# extension-board.net
KiCad netlist of a schematic drawn in EAGLE
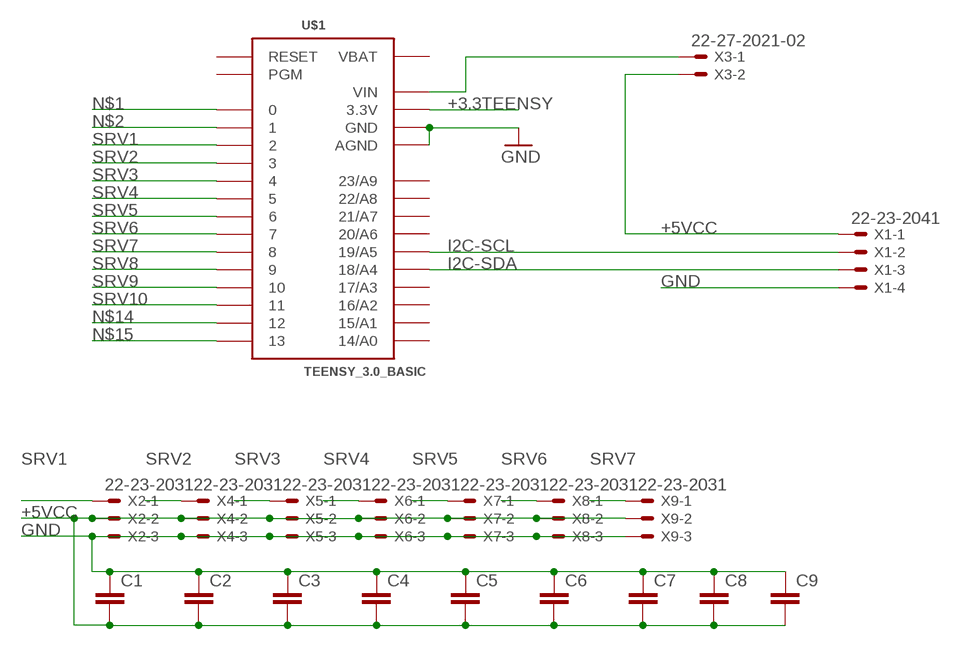
[diagram p0: schematic, sheet 1]

(export (version "E")
  (design (tool "Eeschema 10.0.6"))
  (components
    (comp (ref "C1")
      (value "C-EUC0805K")
      (footprint "eagle-import:C0805K")
      (libsource (lib "eagle-import") (part "C-EUC0805K"))
    )
    (comp (ref "C2")
      (value "C-EUC0805K")
      (footprint "eagle-import:C0805K")
      (libsource (lib "eagle-import") (part "C-EUC0805K"))
    )
    (comp (ref "C3")
      (value "C-EUC0805K")
      (footprint "eagle-import:C0805K")
      (libsource (lib "eagle-import") (part "C-EUC0805K"))
    )
    (comp (ref "C4")
      (value "C-EUC0805K")
      (footprint "eagle-import:C0805K")
      (libsource (lib "eagle-import") (part "C-EUC0805K"))
    )
    (comp (ref "C5")
      (value "C-EUC0805K")
      (footprint "eagle-import:C0805K")
      (libsource (lib "eagle-import") (part "C-EUC0805K"))
    )
    (comp (ref "C6")
      (value "C-EUC0805K")
      (footprint "eagle-import:C0805K")
      (libsource (lib "eagle-import") (part "C-EUC0805K"))
    )
    (comp (ref "C7")
      (value "C-EUC0805K")
      (footprint "eagle-import:C0805K")
      (libsource (lib "eagle-import") (part "C-EUC0805K"))
    )
    (comp (ref "C8")
      (value "C-EUC0805K")
      (footprint "eagle-import:C0805K")
      (libsource (lib "eagle-import") (part "C-EUC0805K"))
    )
    (comp (ref "C9")
      (value "C-EUC0805K")
      (footprint "eagle-import:C0805K")
      (libsource (lib "eagle-import") (part "C-EUC0805K"))
    )
    (comp (ref "U$1")
      (value "TEENSY_3.0_BASIC")
      (footprint "eagle-import:TEENSY_3.0_BASIC")
      (libsource (lib "eagle-import") (part "TEENSY_3.0_BASIC"))
    )
    (comp (ref "X1")
      (value "22-23-2041")
      (footprint "eagle-import:22-23-2041")
      (fields (field (name "MF") "MOLEX"))
      (libsource (lib "eagle-import") (part "22-23-2041"))
    )
    (comp (ref "X2")
      (value "22-23-2031")
      (footprint "eagle-import:22-23-2031")
      (fields (field (name "MF") "MOLEX"))
      (libsource (lib "eagle-import") (part "22-23-2031"))
    )
    (comp (ref "X3")
      (value "22-27-2021-02")
      (footprint "eagle-import:6410-02")
      (libsource (lib "eagle-import") (part "22-?-0227-2021"))
    )
    (comp (ref "X4")
      (value "22-23-2031")
      (footprint "eagle-import:22-23-2031")
      (fields (field (name "MF") "MOLEX"))
      (libsource (lib "eagle-import") (part "22-23-2031"))
    )
    (comp (ref "X5")
      (value "22-23-2031")
      (footprint "eagle-import:22-23-2031")
      (fields (field (name "MF") "MOLEX"))
      (libsource (lib "eagle-import") (part "22-23-2031"))
    )
    (comp (ref "X6")
      (value "22-23-2031")
      (footprint "eagle-import:22-23-2031")
      (fields (field (name "MF") "MOLEX"))
      (libsource (lib "eagle-import") (part "22-23-2031"))
    )
    (comp (ref "X7")
      (value "22-23-2031")
      (footprint "eagle-import:22-23-2031")
      (fields (field (name "MF") "MOLEX"))
      (libsource (lib "eagle-import") (part "22-23-2031"))
    )
    (comp (ref "X8")
      (value "22-23-2031")
      (footprint "eagle-import:22-23-2031")
      (fields (field (name "MF") "MOLEX"))
      (libsource (lib "eagle-import") (part "22-23-2031"))
    )
    (comp (ref "X9")
      (value "22-23-2031")
      (footprint "eagle-import:22-23-2031")
      (fields (field (name "MF") "MOLEX"))
      (libsource (lib "eagle-import") (part "22-23-2031"))
    )
  )
  (nets
    (net (code "1") (name "/+3.3TEENSY") (class "Default")
      (node (ref "U$1") (pin "3.3V") (pinfunction "3.3V_3.3V") (pintype "power_in"))
      (node (ref "U$1") (pin "3.3V1") (pinfunction "3.3V_3.3V1") (pintype "power_in"))
    )
    (net (code "2") (name "/+5VCC") (class "Default")
      (node (ref "C1") (pin "2") (pinfunction "2_2") (pintype "passive"))
      (node (ref "C2") (pin "2") (pinfunction "2_2") (pintype "passive"))
      (node (ref "C3") (pin "2") (pinfunction "2_2") (pintype "passive"))
      (node (ref "C4") (pin "2") (pinfunction "2_2") (pintype "passive"))
      (node (ref "C5") (pin "2") (pinfunction "2_2") (pintype "passive"))
      (node (ref "C6") (pin "2") (pinfunction "2_2") (pintype "passive"))
      (node (ref "C7") (pin "2") (pinfunction "2_2") (pintype "passive"))
      (node (ref "C8") (pin "2") (pinfunction "2_2") (pintype "passive"))
      (node (ref "C9") (pin "2") (pinfunction "2_2") (pintype "passive"))
      (node (ref "X1") (pin "1") (pinfunction "S_1") (pintype "passive"))
      (node (ref "X2") (pin "2") (pinfunction "S_2") (pintype "passive"))
      (node (ref "X3") (pin "2") (pinfunction "S_2") (pintype "passive"))
      (node (ref "X4") (pin "2") (pinfunction "S_2") (pintype "passive"))
      (node (ref "X5") (pin "2") (pinfunction "S_2") (pintype "passive"))
      (node (ref "X6") (pin "2") (pinfunction "S_2") (pintype "passive"))
      (node (ref "X7") (pin "2") (pinfunction "S_2") (pintype "passive"))
      (node (ref "X8") (pin "2") (pinfunction "S_2") (pintype "passive"))
      (node (ref "X9") (pin "2") (pinfunction "S_2") (pintype "passive"))
    )
    (net (code "3") (name "/I2C-SCL") (class "Default")
      (node (ref "U$1") (pin "19/A5") (pinfunction "19/A5_19/A5") (pintype "bidirectional"))
      (node (ref "X1") (pin "2") (pinfunction "S_2") (pintype "passive"))
    )
    (net (code "4") (name "/I2C-SDA") (class "Default")
      (node (ref "U$1") (pin "18/A4") (pinfunction "18/A4_18/A4") (pintype "bidirectional"))
      (node (ref "X1") (pin "3") (pinfunction "S_3") (pintype "passive"))
    )
    (net (code "5") (name "/N$1") (class "Default")
      (node (ref "U$1") (pin "0") (pinfunction "0_0") (pintype "bidirectional"))
    )
    (net (code "6") (name "/N$2") (class "Default")
      (node (ref "U$1") (pin "1") (pinfunction "1_1") (pintype "bidirectional"))
    )
    (net (code "7") (name "/N$14") (class "Default")
      (node (ref "U$1") (pin "12") (pinfunction "12_12") (pintype "bidirectional"))
    )
    (net (code "8") (name "/N$15") (class "Default")
      (node (ref "U$1") (pin "13") (pinfunction "13_13") (pintype "bidirectional"))
    )
    (net (code "9") (name "/SRV1") (class "Default")
      (node (ref "U$1") (pin "2") (pinfunction "2_2") (pintype "bidirectional"))
      (node (ref "X2") (pin "1") (pinfunction "S_1") (pintype "passive"))
    )
    (net (code "10") (name "/SRV2") (class "Default")
      (node (ref "U$1") (pin "3") (pinfunction "3_3") (pintype "bidirectional"))
      (node (ref "X4") (pin "1") (pinfunction "S_1") (pintype "passive"))
    )
    (net (code "11") (name "/SRV3") (class "Default")
      (node (ref "U$1") (pin "4") (pinfunction "4_4") (pintype "bidirectional"))
      (node (ref "X5") (pin "1") (pinfunction "S_1") (pintype "passive"))
    )
    (net (code "12") (name "/SRV4") (class "Default")
      (node (ref "U$1") (pin "5") (pinfunction "5_5") (pintype "bidirectional"))
      (node (ref "X6") (pin "1") (pinfunction "S_1") (pintype "passive"))
    )
    (net (code "13") (name "/SRV5") (class "Default")
      (node (ref "U$1") (pin "6") (pinfunction "6_6") (pintype "bidirectional"))
      (node (ref "X7") (pin "1") (pinfunction "S_1") (pintype "passive"))
    )
    (net (code "14") (name "/SRV6") (class "Default")
      (node (ref "U$1") (pin "7") (pinfunction "7_7") (pintype "bidirectional"))
      (node (ref "X8") (pin "1") (pinfunction "S_1") (pintype "passive"))
    )
    (net (code "15") (name "/SRV7") (class "Default")
      (node (ref "U$1") (pin "8") (pinfunction "8_8") (pintype "bidirectional"))
      (node (ref "X9") (pin "1") (pinfunction "S_1") (pintype "passive"))
    )
    (net (code "16") (name "/SRV8") (class "Default")
      (node (ref "U$1") (pin "9") (pinfunction "9_9") (pintype "bidirectional"))
    )
    (net (code "17") (name "/SRV9") (class "Default")
      (node (ref "U$1") (pin "10") (pinfunction "10_10") (pintype "bidirectional"))
    )
    (net (code "18") (name "/SRV10") (class "Default")
      (node (ref "U$1") (pin "11") (pinfunction "11_11") (pintype "bidirectional"))
    )
    (net (code "19") (name "/VBAT") (class "Default")
      (node (ref "U$1") (pin "VBAT") (pinfunction "VBAT_VBAT") (pintype "power_in"))
    )
    (net (code "20") (name "GND") (class "Default")
      (node (ref "C1") (pin "1") (pinfunction "1_1") (pintype "passive"))
      (node (ref "C2") (pin "1") (pinfunction "1_1") (pintype "passive"))
      (node (ref "C3") (pin "1") (pinfunction "1_1") (pintype "passive"))
      (node (ref "C4") (pin "1") (pinfunction "1_1") (pintype "passive"))
      (node (ref "C5") (pin "1") (pinfunction "1_1") (pintype "passive"))
      (node (ref "C6") (pin "1") (pinfunction "1_1") (pintype "passive"))
      (node (ref "C7") (pin "1") (pinfunction "1_1") (pintype "passive"))
      (node (ref "C8") (pin "1") (pinfunction "1_1") (pintype "passive"))
      (node (ref "C9") (pin "1") (pinfunction "1_1") (pintype "passive"))
      (node (ref "U$1") (pin "AGND") (pinfunction "AGND_AGND") (pintype "power_in"))
      (node (ref "U$1") (pin "GND") (pinfunction "GND_GND") (pintype "power_in"))
      (node (ref "U$1") (pin "GND1") (pinfunction "GND_GND1") (pintype "power_in"))
      (node (ref "X1") (pin "4") (pinfunction "S_4") (pintype "passive"))
      (node (ref "X2") (pin "3") (pinfunction "S_3") (pintype "passive"))
      (node (ref "X4") (pin "3") (pinfunction "S_3") (pintype "passive"))
      (node (ref "X5") (pin "3") (pinfunction "S_3") (pintype "passive"))
      (node (ref "X6") (pin "3") (pinfunction "S_3") (pintype "passive"))
      (node (ref "X7") (pin "3") (pinfunction "S_3") (pintype "passive"))
      (node (ref "X8") (pin "3") (pinfunction "S_3") (pintype "passive"))
      (node (ref "X9") (pin "3") (pinfunction "S_3") (pintype "passive"))
    )
    (net (code "21") (name "Net-(X3A-S)") (class "Default")
      (node (ref "U$1") (pin "VIN") (pinfunction "VIN_VIN") (pintype "power_in"))
      (node (ref "X3") (pin "1") (pinfunction "S_1") (pintype "passive"))
    )
    (net (code "22") (name "unconnected-(U$1-Pad14{slash}A0)") (class "Default")
      (node (ref "U$1") (pin "14/A0") (pinfunction "14/A0_14/A0") (pintype "bidirectional"))
    )
    (net (code "23") (name "unconnected-(U$1-Pad15{slash}A1)") (class "Default")
      (node (ref "U$1") (pin "15/A1") (pinfunction "15/A1_15/A1") (pintype "bidirectional"))
    )
    (net (code "24") (name "unconnected-(U$1-Pad16{slash}A2)") (class "Default")
      (node (ref "U$1") (pin "16/A2") (pinfunction "16/A2_16/A2") (pintype "bidirectional"))
    )
    (net (code "25") (name "unconnected-(U$1-Pad17{slash}A3)") (class "Default")
      (node (ref "U$1") (pin "17/A3") (pinfunction "17/A3_17/A3") (pintype "bidirectional"))
    )
    (net (code "26") (name "unconnected-(U$1-Pad20{slash}A6)") (class "Default")
      (node (ref "U$1") (pin "20/A6") (pinfunction "20/A6_20/A6") (pintype "bidirectional"))
    )
    (net (code "27") (name "unconnected-(U$1-Pad21{slash}A7)") (class "Default")
      (node (ref "U$1") (pin "21/A7") (pinfunction "21/A7_21/A7") (pintype "bidirectional"))
    )
    (net (code "28") (name "unconnected-(U$1-Pad22{slash}A8)") (class "Default")
      (node (ref "U$1") (pin "22/A8") (pinfunction "22/A8_22/A8") (pintype "bidirectional"))
    )
    (net (code "29") (name "unconnected-(U$1-Pad23{slash}A9)") (class "Default")
      (node (ref "U$1") (pin "23/A9") (pinfunction "23/A9_23/A9") (pintype "bidirectional"))
    )
    (net (code "30") (name "unconnected-(U$1-PadPGM)") (class "Default")
      (node (ref "U$1") (pin "PGM") (pinfunction "PGM_PGM") (pintype "bidirectional"))
    )
    (net (code "31") (name "unconnected-(U$1-PadRESET)") (class "Default")
      (node (ref "U$1") (pin "RESET") (pinfunction "RESET_RESET") (pintype "bidirectional"))
    )
  )
)
